# schematic.net
KiCad netlist of a schematic drawn in EasyEDA
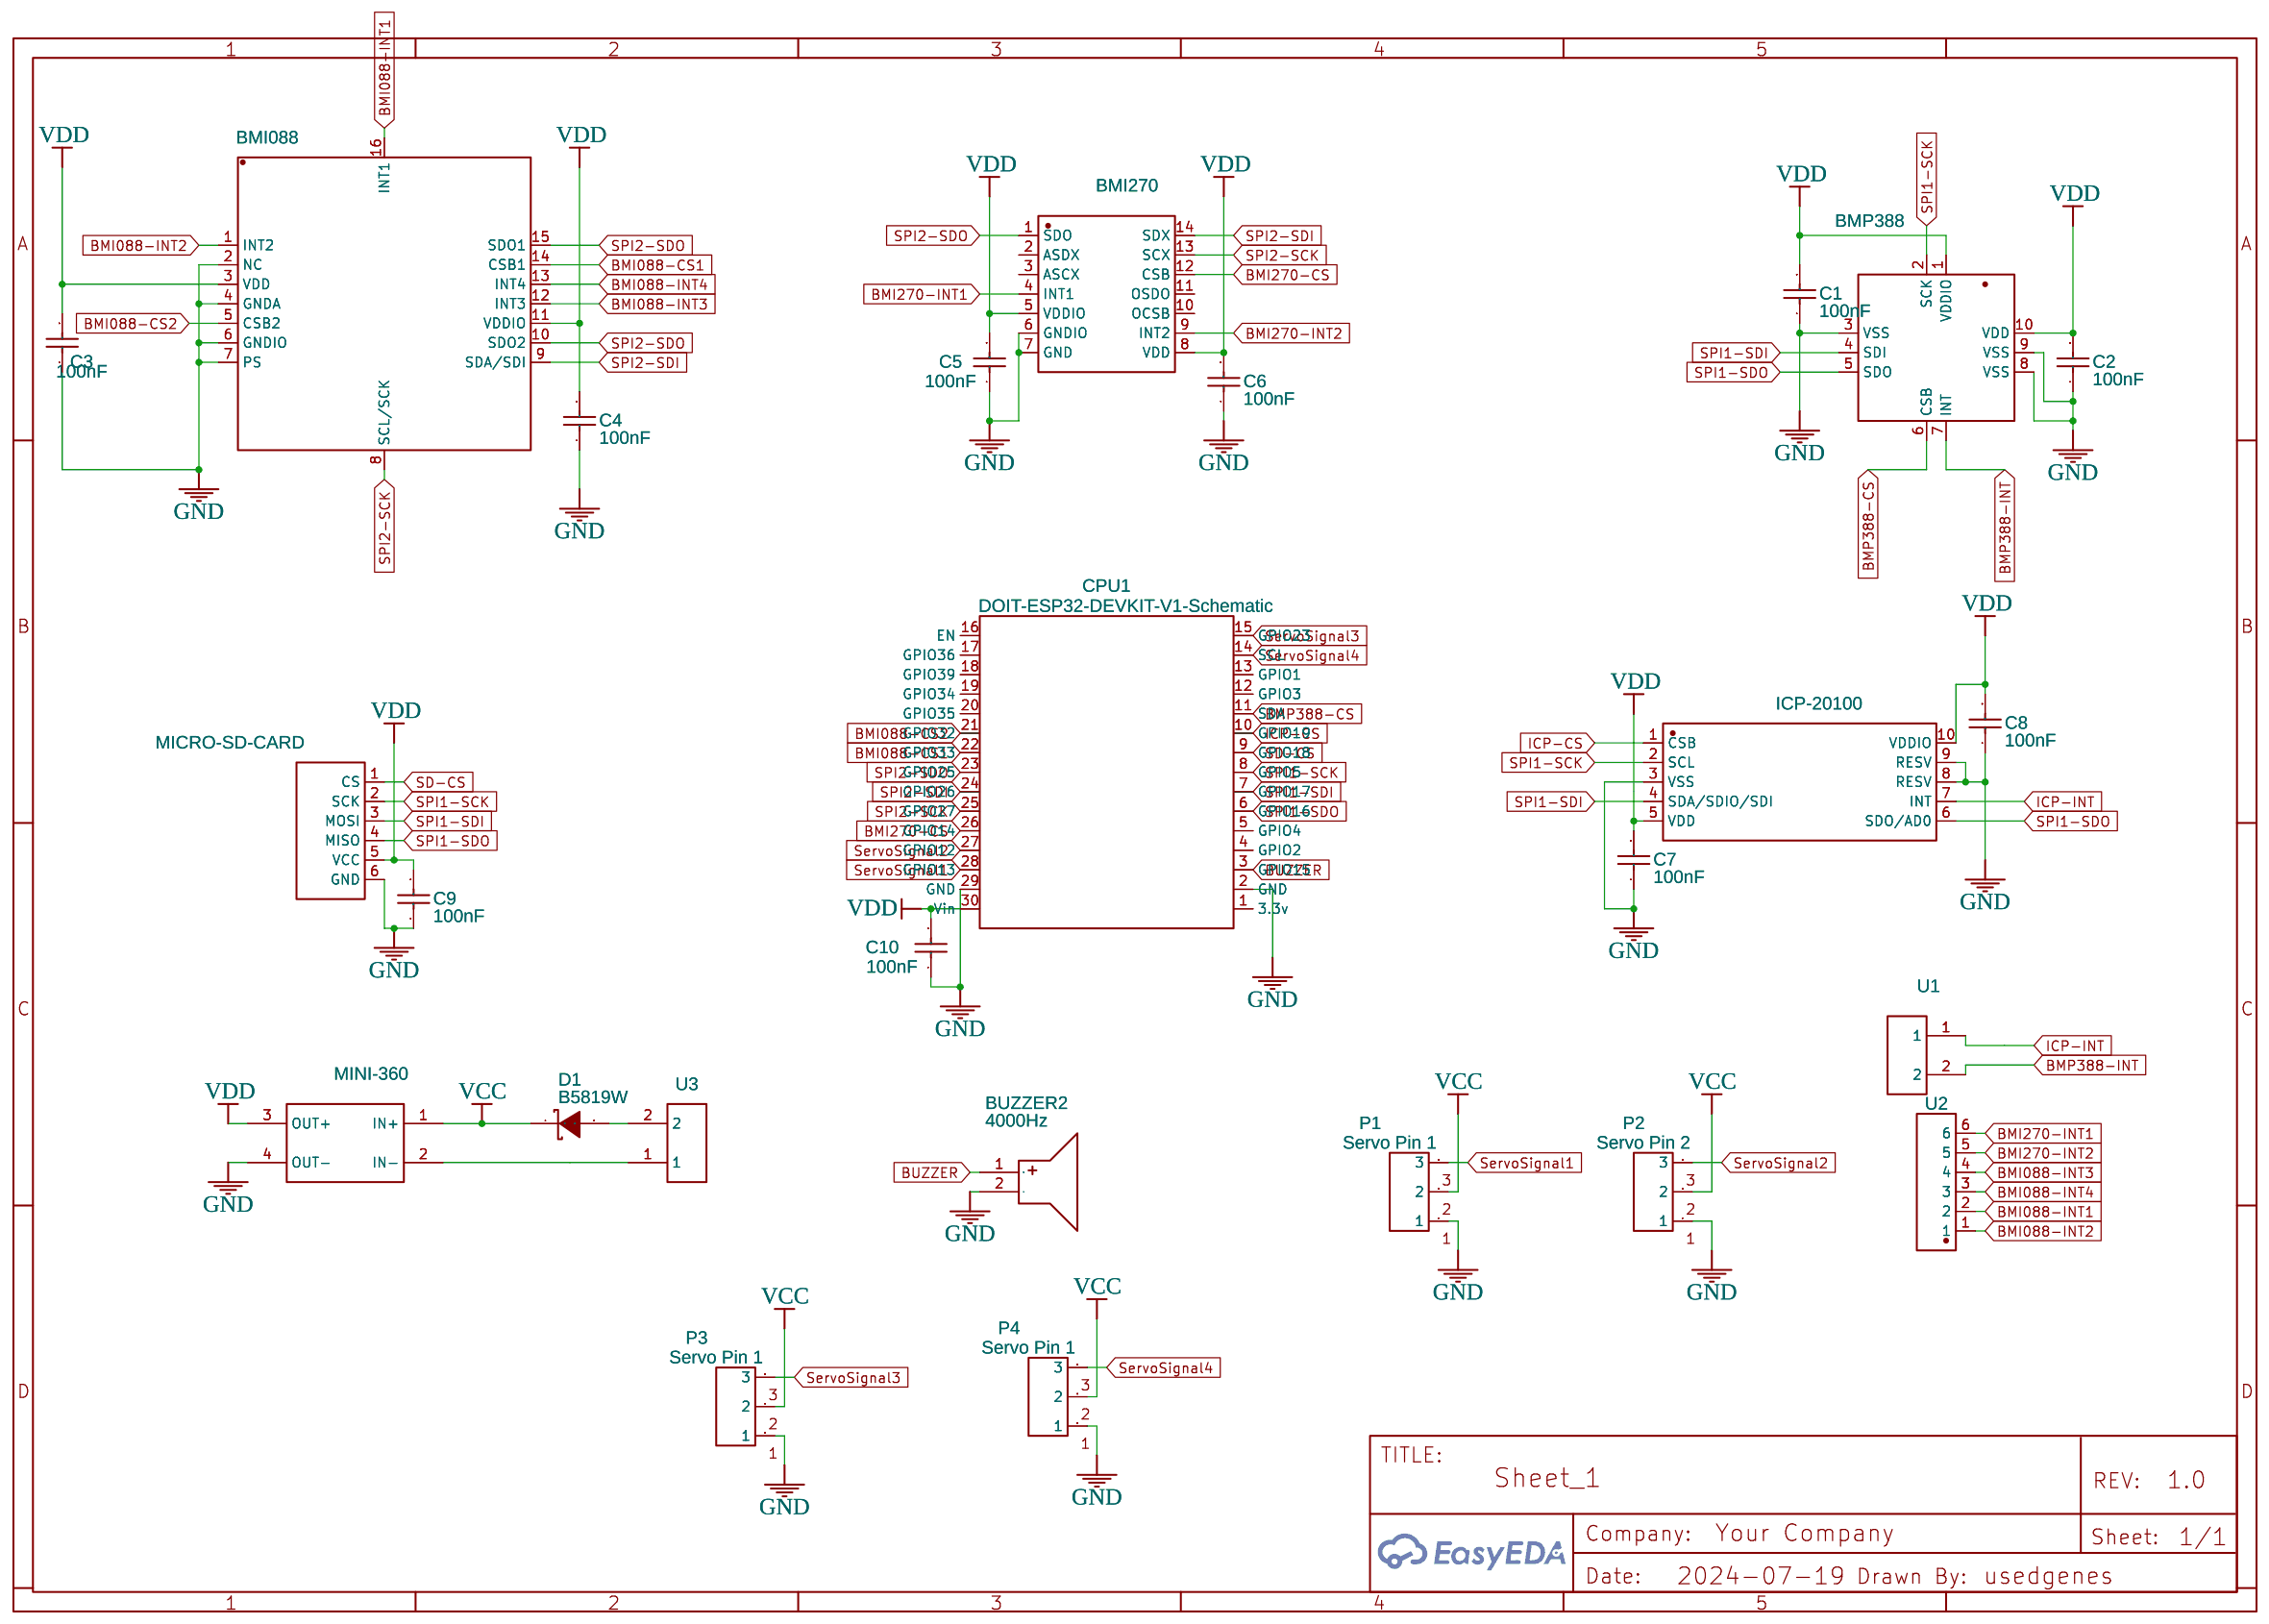
[diagram p0: schematic sheet]

(export (version "E")
  (design (tool "Eeschema 10.0.6"))
  (components
    (comp (ref "BMI088")
      (value "BMI088")
      (fields (field (name "Manufacturer") "Bosch(博世)"))
      (libsource (lib "") (part "BMI088"))
    )
    (comp (ref "BMI270")
      (value "BMI270")
      (fields (field (name "Manufacturer") "Bosch(博世)"))
      (libsource (lib "") (part "BMI270"))
    )
    (comp (ref "BMP388")
      (value "BMP388")
      (fields (field (name "Manufacturer") "Bosch(博世)"))
      (libsource (lib "") (part "BMP388"))
    )
    (comp (ref "BUZZER2")
      (value "4000Hz")
      (fields
        (field (name "Manufacturer Part") "SKY-1475-0540-45P7.6")
        (field (name "Manufacturer") "S&S(海旭)")
      )
      (libsource (lib "") (part "SKY-1475-0540-45P7.6"))
    )
    (comp (ref "C1")
      (value "100nF")
      (fields
        (field (name "Manufacturer Part") "CL05B104KO5NNNC")
        (field (name "Manufacturer") "SAMSUNG(三星)")
      )
      (libsource (lib "") (part "CL05B104KO5NNNC"))
    )
    (comp (ref "C2")
      (value "100nF")
      (fields
        (field (name "Manufacturer Part") "CL05B104KO5NNNC")
        (field (name "Manufacturer") "SAMSUNG(三星)")
      )
      (libsource (lib "") (part "CL05B104KO5NNNC"))
    )
    (comp (ref "C3")
      (value "100nF")
      (fields
        (field (name "Manufacturer Part") "CL05B104KO5NNNC")
        (field (name "Manufacturer") "SAMSUNG(三星)")
      )
      (libsource (lib "") (part "CL05B104KO5NNNC"))
    )
    (comp (ref "C4")
      (value "100nF")
      (fields
        (field (name "Manufacturer Part") "CL05B104KO5NNNC")
        (field (name "Manufacturer") "SAMSUNG(三星)")
      )
      (libsource (lib "") (part "CL05B104KO5NNNC"))
    )
    (comp (ref "C5")
      (value "100nF")
      (fields
        (field (name "Manufacturer Part") "CL05B104KO5NNNC")
        (field (name "Manufacturer") "SAMSUNG(三星)")
      )
      (libsource (lib "") (part "CL05B104KO5NNNC"))
    )
    (comp (ref "C6")
      (value "100nF")
      (fields
        (field (name "Manufacturer Part") "CL05B104KO5NNNC")
        (field (name "Manufacturer") "SAMSUNG(三星)")
      )
      (libsource (lib "") (part "CL05B104KO5NNNC"))
    )
    (comp (ref "C7")
      (value "100nF")
      (fields
        (field (name "Manufacturer Part") "CL05B104KO5NNNC")
        (field (name "Manufacturer") "SAMSUNG(三星)")
      )
      (libsource (lib "") (part "CL05B104KO5NNNC"))
    )
    (comp (ref "C8")
      (value "100nF")
      (fields
        (field (name "Manufacturer Part") "CL05B104KO5NNNC")
        (field (name "Manufacturer") "SAMSUNG(三星)")
      )
      (libsource (lib "") (part "CL05B104KO5NNNC"))
    )
    (comp (ref "C9")
      (value "100nF")
      (fields
        (field (name "Manufacturer Part") "CL05B104KO5NNNC")
        (field (name "Manufacturer") "SAMSUNG(三星)")
      )
      (libsource (lib "") (part "CL05B104KO5NNNC"))
    )
    (comp (ref "C10")
      (value "100nF")
      (fields
        (field (name "Manufacturer Part") "CL05B104KO5NNNC")
        (field (name "Manufacturer") "SAMSUNG(三星)")
      )
      (libsource (lib "") (part "CL05B104KO5NNNC"))
    )
    (comp (ref "CPU1")
      (value "DOIT-ESP32-DEVKIT-V1-Schematic")
      (fields (field (name "Manufacturer Part") "NONE"))
      (libsource (lib "") (part "DOIT-ESP32-DEVKIT-V1-Schematic"))
    )
    (comp (ref "D1")
      (value "B5819W")
      (fields (field (name "Manufacturer") "MDD(辰达半导体)"))
      (libsource (lib "") (part "B5819W"))
    )
    (comp (ref "ICP-20100")
      (value "ICP-20100")
      (fields (field (name "Manufacturer") "TDK"))
      (libsource (lib "") (part "ICP-20100"))
    )
    (comp (ref "MICRO-SD-CARD") (value "MicroSDCardAdapter") (libsource (lib "") (part "MicroSDCardAdapter")))
    (comp (ref "MINI-360") (value "MINI-360") (libsource (lib "") (part "MINI-360")))
    (comp (ref "P1")
      (value "Servo Pin 1")
      (fields
        (field (name "Manufacturer Part") "Female headerHDR1X8-2.54")
        (field (name "Manufacturer") "BOOMELE")
      )
      (libsource (lib "") (part "HEADER PAD 3X RMM COPY"))
    )
    (comp (ref "P2")
      (value "Servo Pin 2")
      (fields
        (field (name "Manufacturer Part") "Female headerHDR1X8-2.54")
        (field (name "Manufacturer") "BOOMELE")
      )
      (libsource (lib "") (part "HEADER PAD 3X RMM COPY"))
    )
    (comp (ref "P3")
      (value "Servo Pin 1")
      (fields
        (field (name "Manufacturer Part") "Female headerHDR1X8-2.54")
        (field (name "Manufacturer") "BOOMELE")
      )
      (libsource (lib "") (part "HEADER PAD 3X RMM COPY"))
    )
    (comp (ref "P4")
      (value "Servo Pin 1")
      (fields
        (field (name "Manufacturer Part") "Female headerHDR1X8-2.54")
        (field (name "Manufacturer") "BOOMELE")
      )
      (libsource (lib "") (part "HEADER PAD 3X RMM COPY"))
    )
    (comp (ref "U1") (value "Power Pins") (libsource (lib "") (part "1X2_1")))
    (comp (ref "U2")
      (value "PIN HEADER 1X6PIN 2.54MM 6P OK COPY")
      (libsource (lib "") (part "PIN HEADER 1X6PIN 2.54MM 6P OK COPY"))
    )
    (comp (ref "U3") (value "Power Pins") (libsource (lib "") (part "1X2")))
  )
  (nets
    (net (code "1") (name "BMI088-CS1") (class "Default")
      (node (ref "BMI088") (pin "14") (pinfunction "CSB1_14") (pintype "unspecified"))
      (node (ref "CPU1") (pin "22") (pinfunction "GPIO33_22") (pintype "unspecified"))
    )
    (net (code "2") (name "BMI088-CS2") (class "Default")
      (node (ref "BMI088") (pin "5") (pinfunction "CSB2_5") (pintype "unspecified"))
      (node (ref "CPU1") (pin "21") (pinfunction "GPIO32_21") (pintype "unspecified"))
    )
    (net (code "3") (name "BMI088-INT1") (class "Default")
      (node (ref "BMI088") (pin "16") (pinfunction "INT1_16") (pintype "unspecified"))
      (node (ref "U2") (pin "2") (pinfunction "2_2") (pintype "unspecified"))
    )
    (net (code "4") (name "BMI088-INT2") (class "Default")
      (node (ref "BMI088") (pin "1") (pinfunction "INT2_1") (pintype "unspecified"))
      (node (ref "U2") (pin "1") (pinfunction "1_1") (pintype "unspecified"))
    )
    (net (code "5") (name "BMI088-INT3") (class "Default")
      (node (ref "BMI088") (pin "12") (pinfunction "INT3_12") (pintype "unspecified"))
      (node (ref "U2") (pin "4") (pinfunction "4_4") (pintype "unspecified"))
    )
    (net (code "6") (name "BMI088-INT4") (class "Default")
      (node (ref "BMI088") (pin "13") (pinfunction "INT4_13") (pintype "unspecified"))
      (node (ref "U2") (pin "3") (pinfunction "3_3") (pintype "unspecified"))
    )
    (net (code "7") (name "BMI270-CS") (class "Default")
      (node (ref "BMI270") (pin "12") (pinfunction "CSB_12") (pintype "unspecified"))
      (node (ref "CPU1") (pin "26") (pinfunction "GPIO14_26") (pintype "unspecified"))
    )
    (net (code "8") (name "BMI270-INT1") (class "Default")
      (node (ref "BMI270") (pin "4") (pinfunction "INT1_4") (pintype "unspecified"))
      (node (ref "U2") (pin "6") (pinfunction "6_6") (pintype "unspecified"))
    )
    (net (code "9") (name "BMI270-INT2") (class "Default")
      (node (ref "BMI270") (pin "9") (pinfunction "INT2_9") (pintype "unspecified"))
      (node (ref "U2") (pin "5") (pinfunction "5_5") (pintype "unspecified"))
    )
    (net (code "10") (name "BMP388-CS") (class "Default")
      (node (ref "BMP388") (pin "6") (pinfunction "CSB_6") (pintype "unspecified"))
      (node (ref "CPU1") (pin "11") (pinfunction "SDA_11") (pintype "unspecified"))
    )
    (net (code "11") (name "BMP388-INT") (class "Default")
      (node (ref "BMP388") (pin "7") (pinfunction "INT_7") (pintype "unspecified"))
      (node (ref "U1") (pin "2") (pinfunction "2_2") (pintype "unspecified"))
    )
    (net (code "12") (name "BUZZER") (class "Default")
      (node (ref "BUZZER2") (pin "1") (pinfunction "+_1") (pintype "unspecified"))
      (node (ref "CPU1") (pin "3") (pinfunction "GPIO15_3") (pintype "unspecified"))
    )
    (net (code "13") (name "GND") (class "Default")
      (node (ref "BMI088") (pin "2") (pinfunction "NC_2") (pintype "unspecified"))
      (node (ref "BMI088") (pin "4") (pinfunction "GNDA_4") (pintype "unspecified"))
      (node (ref "BMI088") (pin "6") (pinfunction "GNDIO_6") (pintype "unspecified"))
      (node (ref "BMI088") (pin "7") (pinfunction "PS_7") (pintype "unspecified"))
      (node (ref "BMI270") (pin "6") (pinfunction "GNDIO_6") (pintype "unspecified"))
      (node (ref "BMI270") (pin "7") (pinfunction "GND_7") (pintype "unspecified"))
      (node (ref "BMP388") (pin "3") (pinfunction "VSS_3") (pintype "unspecified"))
      (node (ref "BMP388") (pin "8") (pinfunction "VSS_8") (pintype "unspecified"))
      (node (ref "BMP388") (pin "9") (pinfunction "VSS_9") (pintype "unspecified"))
      (node (ref "BUZZER2") (pin "2") (pinfunction "-_2") (pintype "unspecified"))
      (node (ref "C1") (pin "1") (pinfunction "1_1") (pintype "input"))
      (node (ref "C10") (pin "1") (pinfunction "1_1") (pintype "input"))
      (node (ref "C2") (pin "1") (pinfunction "1_1") (pintype "input"))
      (node (ref "C3") (pin "1") (pinfunction "1_1") (pintype "input"))
      (node (ref "C4") (pin "1") (pinfunction "1_1") (pintype "input"))
      (node (ref "C5") (pin "1") (pinfunction "1_1") (pintype "input"))
      (node (ref "C6") (pin "1") (pinfunction "1_1") (pintype "input"))
      (node (ref "C7") (pin "1") (pinfunction "1_1") (pintype "input"))
      (node (ref "C8") (pin "1") (pinfunction "1_1") (pintype "input"))
      (node (ref "C9") (pin "1") (pinfunction "1_1") (pintype "input"))
      (node (ref "CPU1") (pin "2") (pinfunction "GND_2") (pintype "unspecified"))
      (node (ref "CPU1") (pin "29") (pinfunction "GND_29") (pintype "unspecified"))
      (node (ref "ICP-20100") (pin "3") (pinfunction "VSS_3") (pintype "unspecified"))
      (node (ref "ICP-20100") (pin "8") (pinfunction "RESV_8") (pintype "unspecified"))
      (node (ref "ICP-20100") (pin "9") (pinfunction "RESV_9") (pintype "unspecified"))
      (node (ref "MICRO-SD-CARD") (pin "6") (pinfunction "GND_6") (pintype "passive"))
      (node (ref "MINI-360") (pin "4") (pinfunction "OUT-_4") (pintype "unspecified"))
      (node (ref "P1") (pin "1") (pinfunction "1_1") (pintype "unspecified"))
      (node (ref "P2") (pin "1") (pinfunction "1_1") (pintype "unspecified"))
      (node (ref "P3") (pin "1") (pinfunction "1_1") (pintype "unspecified"))
      (node (ref "P4") (pin "1") (pinfunction "1_1") (pintype "unspecified"))
    )
    (net (code "14") (name "ICP-CS") (class "Default")
      (node (ref "CPU1") (pin "10") (pinfunction "GPIO19_10") (pintype "unspecified"))
      (node (ref "ICP-20100") (pin "1") (pinfunction "CSB_1") (pintype "unspecified"))
    )
    (net (code "15") (name "ICP-INT") (class "Default")
      (node (ref "ICP-20100") (pin "7") (pinfunction "INT_7") (pintype "unspecified"))
      (node (ref "U1") (pin "1") (pinfunction "1_1") (pintype "unspecified"))
    )
    (net (code "16") (name "Net-(D1-A)") (class "Default")
      (node (ref "D1") (pin "2") (pinfunction "A_2") (pintype "unspecified"))
      (node (ref "U3") (pin "2") (pinfunction "2_2") (pintype "unspecified"))
    )
    (net (code "17") (name "Net-(MINI-360-IN-)") (class "Default")
      (node (ref "MINI-360") (pin "2") (pinfunction "IN-_2") (pintype "unspecified"))
      (node (ref "U3") (pin "1") (pinfunction "1_1") (pintype "unspecified"))
    )
    (net (code "18") (name "SD-CS") (class "Default")
      (node (ref "CPU1") (pin "9") (pinfunction "GPIO18_9") (pintype "unspecified"))
      (node (ref "MICRO-SD-CARD") (pin "1") (pinfunction "CS_1") (pintype "bidirectional"))
    )
    (net (code "19") (name "SPI1-SCK") (class "Default")
      (node (ref "BMP388") (pin "2") (pinfunction "SCK_2") (pintype "unspecified"))
      (node (ref "CPU1") (pin "8") (pinfunction "GPIO5_8") (pintype "unspecified"))
      (node (ref "ICP-20100") (pin "2") (pinfunction "SCL_2") (pintype "unspecified"))
      (node (ref "MICRO-SD-CARD") (pin "2") (pinfunction "SCK_2") (pintype "bidirectional"))
    )
    (net (code "20") (name "SPI1-SDI") (class "Default")
      (node (ref "BMP388") (pin "4") (pinfunction "SDI_4") (pintype "unspecified"))
      (node (ref "CPU1") (pin "7") (pinfunction "GPIO17_7") (pintype "unspecified"))
      (node (ref "ICP-20100") (pin "4") (pinfunction "SDA/SDIO/SDI_4") (pintype "unspecified"))
      (node (ref "MICRO-SD-CARD") (pin "3") (pinfunction "MOSI_3") (pintype "passive"))
    )
    (net (code "21") (name "SPI1-SDO") (class "Default")
      (node (ref "BMP388") (pin "5") (pinfunction "SDO_5") (pintype "unspecified"))
      (node (ref "CPU1") (pin "6") (pinfunction "GPIO16_6") (pintype "unspecified"))
      (node (ref "ICP-20100") (pin "6") (pinfunction "SDO/AD0_6") (pintype "unspecified"))
      (node (ref "MICRO-SD-CARD") (pin "4") (pinfunction "MISO_4") (pintype "bidirectional"))
    )
    (net (code "22") (name "SPI2-SCK") (class "Default")
      (node (ref "BMI088") (pin "8") (pinfunction "SCL/SCK_8") (pintype "unspecified"))
      (node (ref "BMI270") (pin "13") (pinfunction "SCX_13") (pintype "unspecified"))
      (node (ref "CPU1") (pin "25") (pinfunction "GPIO27_25") (pintype "unspecified"))
    )
    (net (code "23") (name "SPI2-SDI") (class "Default")
      (node (ref "BMI088") (pin "9") (pinfunction "SDA/SDI_9") (pintype "unspecified"))
      (node (ref "BMI270") (pin "14") (pinfunction "SDX_14") (pintype "unspecified"))
      (node (ref "CPU1") (pin "24") (pinfunction "GPIO26_24") (pintype "unspecified"))
    )
    (net (code "24") (name "SPI2-SDO") (class "Default")
      (node (ref "BMI088") (pin "10") (pinfunction "SDO2_10") (pintype "unspecified"))
      (node (ref "BMI088") (pin "15") (pinfunction "SDO1_15") (pintype "unspecified"))
      (node (ref "BMI270") (pin "1") (pinfunction "SDO_1") (pintype "unspecified"))
      (node (ref "CPU1") (pin "23") (pinfunction "GPIO25_23") (pintype "unspecified"))
    )
    (net (code "25") (name "ServoSignal1") (class "Default")
      (node (ref "CPU1") (pin "28") (pinfunction "GPIO13_28") (pintype "unspecified"))
      (node (ref "P1") (pin "3") (pinfunction "3_3") (pintype "unspecified"))
    )
    (net (code "26") (name "ServoSignal2") (class "Default")
      (node (ref "CPU1") (pin "27") (pinfunction "GPIO12_27") (pintype "unspecified"))
      (node (ref "P2") (pin "3") (pinfunction "3_3") (pintype "unspecified"))
    )
    (net (code "27") (name "ServoSignal3") (class "Default")
      (node (ref "CPU1") (pin "15") (pinfunction "GPIO23_15") (pintype "unspecified"))
      (node (ref "P3") (pin "3") (pinfunction "3_3") (pintype "unspecified"))
    )
    (net (code "28") (name "ServoSignal4") (class "Default")
      (node (ref "CPU1") (pin "14") (pinfunction "SCL_14") (pintype "unspecified"))
      (node (ref "P4") (pin "3") (pinfunction "3_3") (pintype "unspecified"))
    )
    (net (code "29") (name "VCC") (class "Default")
      (node (ref "D1") (pin "1") (pinfunction "K_1") (pintype "unspecified"))
      (node (ref "MINI-360") (pin "1") (pinfunction "IN+_1") (pintype "unspecified"))
      (node (ref "P1") (pin "2") (pinfunction "2_2") (pintype "unspecified"))
      (node (ref "P2") (pin "2") (pinfunction "2_2") (pintype "unspecified"))
      (node (ref "P3") (pin "2") (pinfunction "2_2") (pintype "unspecified"))
      (node (ref "P4") (pin "2") (pinfunction "2_2") (pintype "unspecified"))
    )
    (net (code "30") (name "VDD") (class "Default")
      (node (ref "BMI088") (pin "11") (pinfunction "VDDIO_11") (pintype "unspecified"))
      (node (ref "BMI088") (pin "3") (pinfunction "VDD_3") (pintype "unspecified"))
      (node (ref "BMI270") (pin "5") (pinfunction "VDDIO_5") (pintype "unspecified"))
      (node (ref "BMI270") (pin "8") (pinfunction "VDD_8") (pintype "unspecified"))
      (node (ref "BMP388") (pin "1") (pinfunction "VDDIO_1") (pintype "unspecified"))
      (node (ref "BMP388") (pin "10") (pinfunction "VDD_10") (pintype "unspecified"))
      (node (ref "C1") (pin "2") (pinfunction "2_2") (pintype "input"))
      (node (ref "C10") (pin "2") (pinfunction "2_2") (pintype "input"))
      (node (ref "C2") (pin "2") (pinfunction "2_2") (pintype "input"))
      (node (ref "C3") (pin "2") (pinfunction "2_2") (pintype "input"))
      (node (ref "C4") (pin "2") (pinfunction "2_2") (pintype "input"))
      (node (ref "C5") (pin "2") (pinfunction "2_2") (pintype "input"))
      (node (ref "C6") (pin "2") (pinfunction "2_2") (pintype "input"))
      (node (ref "C7") (pin "2") (pinfunction "2_2") (pintype "input"))
      (node (ref "C8") (pin "2") (pinfunction "2_2") (pintype "input"))
      (node (ref "C9") (pin "2") (pinfunction "2_2") (pintype "input"))
      (node (ref "CPU1") (pin "30") (pinfunction "Vin_30") (pintype "unspecified"))
      (node (ref "ICP-20100") (pin "10") (pinfunction "VDDIO_10") (pintype "unspecified"))
      (node (ref "ICP-20100") (pin "5") (pinfunction "VDD_5") (pintype "unspecified"))
      (node (ref "MICRO-SD-CARD") (pin "5") (pinfunction "VCC_5") (pintype "passive"))
      (node (ref "MINI-360") (pin "3") (pinfunction "OUT+_3") (pintype "unspecified"))
    )
    (net (code "31") (name "unconnected-(BMI270-ASCX-Pad3)") (class "Default")
      (node (ref "BMI270") (pin "3") (pinfunction "ASCX_3") (pintype "unspecified"))
    )
    (net (code "32") (name "unconnected-(BMI270-ASDX-Pad2)") (class "Default")
      (node (ref "BMI270") (pin "2") (pinfunction "ASDX_2") (pintype "unspecified"))
    )
    (net (code "33") (name "unconnected-(BMI270-OCSB-Pad10)") (class "Default")
      (node (ref "BMI270") (pin "10") (pinfunction "OCSB_10") (pintype "unspecified"))
    )
    (net (code "34") (name "unconnected-(BMI270-OSDO-Pad11)") (class "Default")
      (node (ref "BMI270") (pin "11") (pinfunction "OSDO_11") (pintype "unspecified"))
    )
    (net (code "35") (name "unconnected-(CPU1-3.3v-Pad1)") (class "Default")
      (node (ref "CPU1") (pin "1") (pinfunction "3.3v_1") (pintype "unspecified"))
    )
    (net (code "36") (name "unconnected-(CPU1-EN-Pad16)") (class "Default")
      (node (ref "CPU1") (pin "16") (pinfunction "EN_16") (pintype "unspecified"))
    )
    (net (code "37") (name "unconnected-(CPU1-GPIO1-Pad13)") (class "Default")
      (node (ref "CPU1") (pin "13") (pinfunction "GPIO1_13") (pintype "unspecified"))
    )
    (net (code "38") (name "unconnected-(CPU1-GPIO2-Pad4)") (class "Default")
      (node (ref "CPU1") (pin "4") (pinfunction "GPIO2_4") (pintype "unspecified"))
    )
    (net (code "39") (name "unconnected-(CPU1-GPIO3-Pad12)") (class "Default")
      (node (ref "CPU1") (pin "12") (pinfunction "GPIO3_12") (pintype "unspecified"))
    )
    (net (code "40") (name "unconnected-(CPU1-GPIO4-Pad5)") (class "Default")
      (node (ref "CPU1") (pin "5") (pinfunction "GPIO4_5") (pintype "unspecified"))
    )
    (net (code "41") (name "unconnected-(CPU1-GPIO34-Pad19)") (class "Default")
      (node (ref "CPU1") (pin "19") (pinfunction "GPIO34_19") (pintype "unspecified"))
    )
    (net (code "42") (name "unconnected-(CPU1-GPIO35-Pad20)") (class "Default")
      (node (ref "CPU1") (pin "20") (pinfunction "GPIO35_20") (pintype "unspecified"))
    )
    (net (code "43") (name "unconnected-(CPU1-GPIO36-Pad17)") (class "Default")
      (node (ref "CPU1") (pin "17") (pinfunction "GPIO36_17") (pintype "unspecified"))
    )
    (net (code "44") (name "unconnected-(CPU1-GPIO39-Pad18)") (class "Default")
      (node (ref "CPU1") (pin "18") (pinfunction "GPIO39_18") (pintype "unspecified"))
    )
  )
)
